# Controller.net
KiCad netlist of a schematic drawn in Altium Designer
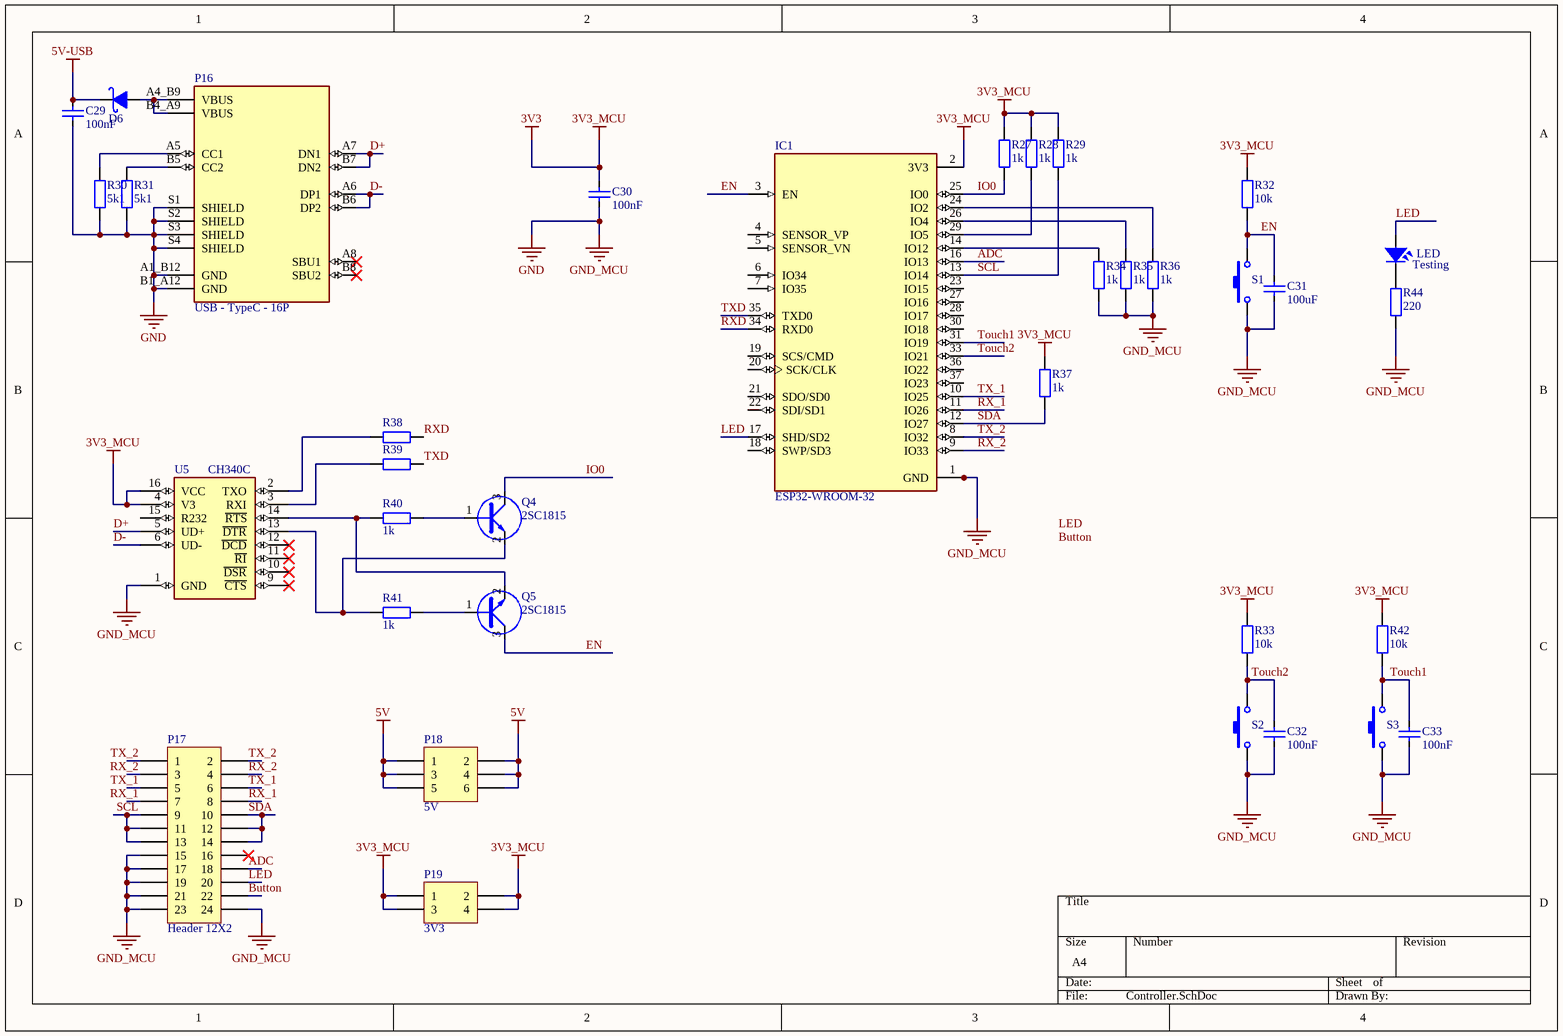
[diagram p0: Controller.SchDoc]

(export (version "E")
  (design (tool "Eeschema 10.0.6"))
  (components
    (comp (ref "C29")
      (value "100nF")
      (footprint "CAP_0805")
      (description "C 0805")
      (fields (field (name "PUBLISHER") "Altium Limited"))
      (libsource (lib "My Library") (part "CapSMD"))
    )
    (comp (ref "C30")
      (value "100nF")
      (footprint "CAP_0805")
      (description "C 0805")
      (fields (field (name "PUBLISHER") "Altium Limited"))
      (libsource (lib "My Library") (part "CapSMD"))
    )
    (comp (ref "C31")
      (value "100uF")
      (footprint "CAP_0805")
      (description "C 0805")
      (fields (field (name "PUBLISHER") "Altium Limited"))
      (libsource (lib "My Library") (part "CapSMD"))
    )
    (comp (ref "C32")
      (value "100nF")
      (footprint "CAP_0805")
      (description "C 0805")
      (fields (field (name "PUBLISHER") "Altium Limited"))
      (libsource (lib "My Library") (part "CapSMD"))
    )
    (comp (ref "C33")
      (value "100nF")
      (footprint "CAP_0805")
      (description "C 0805")
      (fields (field (name "PUBLISHER") "Altium Limited"))
      (libsource (lib "My Library") (part "CapSMD"))
    )
    (comp (ref "D6")
      (value "Diode Schottky")
      (footprint "My Library:DIO-214AA(SMB)")
      (description "SS54")
      (libsource (lib "My Library") (part "Diode Schottky"))
    )
    (comp (ref "IC1")
      (value "ESP32-WROOM-32")
      (footprint "MODULE_ESP32-WROOM-32")
      (description "Bluetooth, WiFi Transceiver Module 2.4GHz ~ 2.5GHz Surface Mount")
      (fields (field (name "MF") "Espressif Systems") (field (name "DIGI-KEY_PART_NUMBER") "1904-1010-1-ND"))
      (libsource (lib "My Library") (part "ESP32-WROOM-32"))
    )
    (comp (ref "LED")
      (value "Testing")
      (footprint "LED-0805-Blue")
      (description "LED Single colour Green and Red")
      (libsource (lib "My Library") (part "LED"))
    )
    (comp (ref "P16")
      (value "USB - TypeC - 16P")
      (footprint "My Library:USB C 16P")
      (libsource (lib "My Library") (part "USB - TypeC - 16P"))
    )
    (comp (ref "P17")
      (value "Header 12X2")
      (footprint "HDR2X12")
      (description "Header, 12-Pin, Dual row")
      (fields (field (name "PUBLISHER") "Altium Limited"))
      (libsource (lib "My Library") (part "Header 12X2"))
    )
    (comp (ref "P18")
      (value "5V")
      (footprint "HDR2X3")
      (description "Header, 3-Pin, Dual row")
      (fields (field (name "PUBLISHER") "Altium Limited"))
      (libsource (lib "My Library") (part "Header 3X2"))
    )
    (comp (ref "P19")
      (value "3V3")
      (footprint "HDR2X2")
      (description "Header, 2-Pin, Dual row")
      (fields (field (name "PUBLISHER") "Altium Limited"))
      (libsource (lib "My Library") (part "Header 2X2"))
    )
    (comp (ref "Q4")
      (value "2SC1815")
      (footprint "SOT23D")
      (description "NPN 600mW, ECB")
      (libsource (lib "My Library") (part "C1815"))
    )
    (comp (ref "Q5")
      (value "2SC1815")
      (footprint "SOT23D")
      (description "NPN 600mW, ECB")
      (libsource (lib "") (part "C1815_1"))
    )
    (comp (ref "R27")
      (value "1k")
      (footprint "RES-SMD-0805")
      (description "R 0805")
      (fields
        (field (name "MANUFACTURER") "Generic Components")
        (field (name "PUBLISHER") "Altium Hobart Technology Centre")
      )
      (libsource (lib "My Library") (part "Resistor - SMD"))
    )
    (comp (ref "R28")
      (value "1k")
      (footprint "RES-SMD-0805")
      (description "R 0805")
      (fields
        (field (name "MANUFACTURER") "Generic Components")
        (field (name "PUBLISHER") "Altium Hobart Technology Centre")
      )
      (libsource (lib "My Library") (part "Resistor - SMD"))
    )
    (comp (ref "R29")
      (value "1k")
      (footprint "RES-SMD-0805")
      (description "R 0805")
      (fields
        (field (name "MANUFACTURER") "Generic Components")
        (field (name "PUBLISHER") "Altium Hobart Technology Centre")
      )
      (libsource (lib "My Library") (part "Resistor - SMD"))
    )
    (comp (ref "R30")
      (value "5k1")
      (footprint "RES-SMD-0805")
      (description "R 0805")
      (fields
        (field (name "MANUFACTURER") "Generic Components")
        (field (name "PUBLISHER") "Altium Hobart Technology Centre")
      )
      (libsource (lib "My Library") (part "Resistor - SMD"))
    )
    (comp (ref "R31")
      (value "5k1")
      (footprint "RES-SMD-0805")
      (description "R 0805")
      (fields
        (field (name "MANUFACTURER") "Generic Components")
        (field (name "PUBLISHER") "Altium Hobart Technology Centre")
      )
      (libsource (lib "My Library") (part "Resistor - SMD"))
    )
    (comp (ref "R32")
      (value "10k")
      (footprint "RES-SMD-0805")
      (description "R 0805")
      (fields
        (field (name "MANUFACTURER") "Generic Components")
        (field (name "PUBLISHER") "Altium Hobart Technology Centre")
      )
      (libsource (lib "My Library") (part "Resistor - SMD"))
    )
    (comp (ref "R33")
      (value "10k")
      (footprint "RES-SMD-0805")
      (description "R 0805")
      (fields
        (field (name "MANUFACTURER") "Generic Components")
        (field (name "PUBLISHER") "Altium Hobart Technology Centre")
      )
      (libsource (lib "My Library") (part "Resistor - SMD"))
    )
    (comp (ref "R34")
      (value "1k")
      (footprint "RES-SMD-0805")
      (description "R 0805")
      (fields
        (field (name "MANUFACTURER") "Generic Components")
        (field (name "PUBLISHER") "Altium Hobart Technology Centre")
      )
      (libsource (lib "My Library") (part "Resistor - SMD"))
    )
    (comp (ref "R35")
      (value "1k")
      (footprint "RES-SMD-0805")
      (description "R 0805")
      (fields
        (field (name "MANUFACTURER") "Generic Components")
        (field (name "PUBLISHER") "Altium Hobart Technology Centre")
      )
      (libsource (lib "My Library") (part "Resistor - SMD"))
    )
    (comp (ref "R36")
      (value "1k")
      (footprint "RES-SMD-0805")
      (description "R 0805")
      (fields
        (field (name "MANUFACTURER") "Generic Components")
        (field (name "PUBLISHER") "Altium Hobart Technology Centre")
      )
      (libsource (lib "My Library") (part "Resistor - SMD"))
    )
    (comp (ref "R37")
      (value "1k")
      (footprint "RES-SMD-0805")
      (description "R 0805")
      (fields
        (field (name "MANUFACTURER") "Generic Components")
        (field (name "PUBLISHER") "Altium Hobart Technology Centre")
      )
      (libsource (lib "My Library") (part "Resistor - SMD"))
    )
    (comp (ref "R38")
      (value "0R")
      (footprint "RES-SMD-0805")
      (description "R 0805")
      (fields
        (field (name "MANUFACTURER") "Generic Components")
        (field (name "PUBLISHER") "Altium Hobart Technology Centre")
      )
      (libsource (lib "My Library") (part "Resistor - SMD"))
    )
    (comp (ref "R39")
      (value "0R")
      (footprint "RES-SMD-0805")
      (description "R 0805")
      (fields
        (field (name "MANUFACTURER") "Generic Components")
        (field (name "PUBLISHER") "Altium Hobart Technology Centre")
      )
      (libsource (lib "My Library") (part "Resistor - SMD"))
    )
    (comp (ref "R40")
      (value "1k")
      (footprint "RES-SMD-0805")
      (description "R 0805")
      (fields
        (field (name "MANUFACTURER") "Generic Components")
        (field (name "PUBLISHER") "Altium Hobart Technology Centre")
      )
      (libsource (lib "My Library") (part "Resistor - SMD"))
    )
    (comp (ref "R41")
      (value "1k")
      (footprint "RES-SMD-0805")
      (description "R 0805")
      (fields
        (field (name "MANUFACTURER") "Generic Components")
        (field (name "PUBLISHER") "Altium Hobart Technology Centre")
      )
      (libsource (lib "My Library") (part "Resistor - SMD"))
    )
    (comp (ref "R42")
      (value "10k")
      (footprint "RES-SMD-0805")
      (description "R 0805")
      (fields
        (field (name "MANUFACTURER") "Generic Components")
        (field (name "PUBLISHER") "Altium Hobart Technology Centre")
      )
      (libsource (lib "My Library") (part "Resistor - SMD"))
    )
    (comp (ref "R44")
      (value "220")
      (footprint "RES-SMD-0805")
      (description "R 0805")
      (fields
        (field (name "MANUFACTURER") "Generic Components")
        (field (name "PUBLISHER") "Altium Hobart Technology Centre")
      )
      (libsource (lib "My Library") (part "Resistor - SMD"))
    )
    (comp (ref "S1")
      (value "SW-SMD")
      (footprint "SW 3x2x4")
      (description "Switch")
      (fields (field (name "PUBLISHER") "Altium Limited"))
      (libsource (lib "My Library") (part "SW-SMD"))
    )
    (comp (ref "S2")
      (value "SW-SMD")
      (footprint "SW 3x2x4")
      (description "Switch")
      (fields (field (name "PUBLISHER") "Altium Limited"))
      (libsource (lib "My Library") (part "SW-SMD"))
    )
    (comp (ref "S3")
      (value "SW-SMD")
      (footprint "SW 3x2x4")
      (description "Switch")
      (fields (field (name "PUBLISHER") "Altium Limited"))
      (libsource (lib "My Library") (part "SW-SMD"))
    )
    (comp (ref "U5")
      (value "CH340C")
      (footprint "SOP-16")
      (description "USB to serial chip CH340")
      (fields (field (name "MF") "WCH"))
      (libsource (lib "My Library") (part "CH340C"))
    )
  )
  (nets
    (net (code "1") (name "/ADC") (class "Default")
      (node (ref "IC1") (pin "16") (pinfunction "IO13_16") (pintype "bidirectional"))
      (node (ref "P17") (pin "18") (pinfunction "18_18") (pintype "passive"))
    )
    (net (code "2") (name "/Button") (class "Default")
      (node (ref "P17") (pin "22") (pinfunction "22_22") (pintype "passive"))
    )
    (net (code "3") (name "/D+") (class "Default")
      (node (ref "P16") (pin "A7") (pinfunction "DN1_A7") (pintype "bidirectional"))
      (node (ref "P16") (pin "B7") (pinfunction "DN2_B7") (pintype "bidirectional"))
      (node (ref "U5") (pin "5") (pinfunction "UD+_5") (pintype "bidirectional"))
    )
    (net (code "4") (name "/D-") (class "Default")
      (node (ref "P16") (pin "A6") (pinfunction "DP1_A6") (pintype "bidirectional"))
      (node (ref "P16") (pin "B6") (pinfunction "DP2_B6") (pintype "bidirectional"))
      (node (ref "U5") (pin "6") (pinfunction "UD-_6") (pintype "bidirectional"))
    )
    (net (code "5") (name "/EN") (class "Default")
      (node (ref "C31") (pin "2") (pinfunction "2_2") (pintype "passive"))
      (node (ref "IC1") (pin "3") (pinfunction "EN_3") (pintype "input"))
      (node (ref "Q5") (pin "3") (pinfunction "C_3") (pintype "passive"))
      (node (ref "R32") (pin "2") (pinfunction "2_2") (pintype "passive"))
      (node (ref "S1") (pin "2") (pinfunction "2_2") (pintype "passive"))
    )
    (net (code "6") (name "/IO0") (class "Default")
      (node (ref "IC1") (pin "25") (pinfunction "IO0_25") (pintype "bidirectional"))
      (node (ref "Q4") (pin "3") (pinfunction "C_3") (pintype "passive"))
      (node (ref "R27") (pin "2") (pinfunction "2_2") (pintype "passive"))
    )
    (net (code "7") (name "/LED") (class "Default")
      (node (ref "IC1") (pin "17") (pinfunction "SHD/SD2_17") (pintype "bidirectional"))
      (node (ref "LED") (pin "1") (pinfunction "1_1") (pintype "passive"))
      (node (ref "P17") (pin "20") (pinfunction "20_20") (pintype "passive"))
    )
    (net (code "8") (name "/RXD") (class "Default")
      (node (ref "IC1") (pin "34") (pinfunction "RXD0_34") (pintype "bidirectional"))
      (node (ref "R38") (pin "1") (pinfunction "1_1") (pintype "passive"))
    )
    (net (code "9") (name "/RX_1") (class "Default")
      (node (ref "IC1") (pin "11") (pinfunction "IO26_11") (pintype "bidirectional"))
      (node (ref "P17") (pin "7") (pinfunction "7_7") (pintype "passive"))
      (node (ref "P17") (pin "8") (pinfunction "8_8") (pintype "passive"))
    )
    (net (code "10") (name "/RX_2") (class "Default")
      (node (ref "IC1") (pin "9") (pinfunction "IO33_9") (pintype "bidirectional"))
      (node (ref "P17") (pin "3") (pinfunction "3_3") (pintype "passive"))
      (node (ref "P17") (pin "4") (pinfunction "4_4") (pintype "passive"))
    )
    (net (code "11") (name "/SCL") (class "Default")
      (node (ref "IC1") (pin "13") (pinfunction "IO14_13") (pintype "bidirectional"))
      (node (ref "P17") (pin "11") (pinfunction "11_11") (pintype "passive"))
      (node (ref "P17") (pin "13") (pinfunction "13_13") (pintype "passive"))
      (node (ref "P17") (pin "9") (pinfunction "9_9") (pintype "passive"))
      (node (ref "R29") (pin "2") (pinfunction "2_2") (pintype "passive"))
    )
    (net (code "12") (name "/SDA") (class "Default")
      (node (ref "IC1") (pin "12") (pinfunction "IO27_12") (pintype "bidirectional"))
      (node (ref "P17") (pin "10") (pinfunction "10_10") (pintype "passive"))
      (node (ref "P17") (pin "12") (pinfunction "12_12") (pintype "passive"))
      (node (ref "P17") (pin "14") (pinfunction "14_14") (pintype "passive"))
      (node (ref "R37") (pin "2") (pinfunction "2_2") (pintype "passive"))
    )
    (net (code "13") (name "/TXD") (class "Default")
      (node (ref "IC1") (pin "35") (pinfunction "TXD0_35") (pintype "bidirectional"))
      (node (ref "R39") (pin "1") (pinfunction "1_1") (pintype "passive"))
    )
    (net (code "14") (name "/TX_1") (class "Default")
      (node (ref "IC1") (pin "10") (pinfunction "IO25_10") (pintype "bidirectional"))
      (node (ref "P17") (pin "5") (pinfunction "5_5") (pintype "passive"))
      (node (ref "P17") (pin "6") (pinfunction "6_6") (pintype "passive"))
    )
    (net (code "15") (name "/TX_2") (class "Default")
      (node (ref "IC1") (pin "8") (pinfunction "IO32_8") (pintype "bidirectional"))
      (node (ref "P17") (pin "1") (pinfunction "1_1") (pintype "passive"))
      (node (ref "P17") (pin "2") (pinfunction "2_2") (pintype "passive"))
    )
    (net (code "16") (name "/Touch1") (class "Default")
      (node (ref "C33") (pin "2") (pinfunction "2_2") (pintype "passive"))
      (node (ref "IC1") (pin "31") (pinfunction "IO19_31") (pintype "bidirectional"))
      (node (ref "R42") (pin "2") (pinfunction "2_2") (pintype "passive"))
      (node (ref "S3") (pin "2") (pinfunction "2_2") (pintype "passive"))
    )
    (net (code "17") (name "/Touch2") (class "Default")
      (node (ref "C32") (pin "2") (pinfunction "2_2") (pintype "passive"))
      (node (ref "IC1") (pin "33") (pinfunction "IO21_33") (pintype "bidirectional"))
      (node (ref "R33") (pin "2") (pinfunction "2_2") (pintype "passive"))
      (node (ref "S2") (pin "2") (pinfunction "2_2") (pintype "passive"))
    )
    (net (code "18") (name "3V3") (class "Default")
      (node (ref "C30") (pin "2") (pinfunction "2_2") (pintype "passive"))
      (node (ref "IC1") (pin "2") (pinfunction "3V3_2") (pintype "power_in"))
      (node (ref "P19") (pin "1") (pinfunction "1_1") (pintype "passive"))
      (node (ref "P19") (pin "2") (pinfunction "2_2") (pintype "passive"))
      (node (ref "P19") (pin "3") (pinfunction "3_3") (pintype "passive"))
      (node (ref "P19") (pin "4") (pinfunction "4_4") (pintype "passive"))
      (node (ref "R27") (pin "1") (pinfunction "1_1") (pintype "passive"))
      (node (ref "R28") (pin "1") (pinfunction "1_1") (pintype "passive"))
      (node (ref "R29") (pin "1") (pinfunction "1_1") (pintype "passive"))
      (node (ref "R32") (pin "1") (pinfunction "1_1") (pintype "passive"))
      (node (ref "R33") (pin "1") (pinfunction "1_1") (pintype "passive"))
      (node (ref "R37") (pin "1") (pinfunction "1_1") (pintype "passive"))
      (node (ref "R42") (pin "1") (pinfunction "1_1") (pintype "passive"))
      (node (ref "U5") (pin "16") (pinfunction "VCC_16") (pintype "bidirectional"))
      (node (ref "U5") (pin "4") (pinfunction "V3_4") (pintype "bidirectional"))
    )
    (net (code "19") (name "5V") (class "Default")
      (node (ref "P18") (pin "1") (pinfunction "1_1") (pintype "passive"))
      (node (ref "P18") (pin "2") (pinfunction "2_2") (pintype "passive"))
      (node (ref "P18") (pin "3") (pinfunction "3_3") (pintype "passive"))
      (node (ref "P18") (pin "4") (pinfunction "4_4") (pintype "passive"))
      (node (ref "P18") (pin "5") (pinfunction "5_5") (pintype "passive"))
      (node (ref "P18") (pin "6") (pinfunction "6_6") (pintype "passive"))
    )
    (net (code "20") (name "5V-USB") (class "Default")
      (node (ref "C29") (pin "2") (pinfunction "2_2") (pintype "passive"))
      (node (ref "D6") (pin "2") (pinfunction "K_2") (pintype "passive"))
    )
    (net (code "21") (name "GND") (class "Default")
      (node (ref "C29") (pin "1") (pinfunction "1_1") (pintype "passive"))
      (node (ref "C30") (pin "1") (pinfunction "1_1") (pintype "passive"))
      (node (ref "C31") (pin "1") (pinfunction "1_1") (pintype "passive"))
      (node (ref "C32") (pin "1") (pinfunction "1_1") (pintype "passive"))
      (node (ref "C33") (pin "1") (pinfunction "1_1") (pintype "passive"))
      (node (ref "IC1") (pin "1") (pinfunction "GND_1") (pintype "power_in"))
      (node (ref "IC1") (pin "15") (pinfunction "GND_15") (pintype "power_in"))
      (node (ref "IC1") (pin "38") (pinfunction "GND_38") (pintype "power_in"))
      (node (ref "IC1") (pin "39_1") (pinfunction "GND_39_1") (pintype "power_in"))
      (node (ref "IC1") (pin "39_10") (pinfunction "GND_39_10") (pintype "power_in"))
      (node (ref "IC1") (pin "39_11") (pinfunction "GND_39_11") (pintype "power_in"))
      (node (ref "IC1") (pin "39_12") (pinfunction "GND_39_12") (pintype "power_in"))
      (node (ref "IC1") (pin "39_13") (pinfunction "GND_39_13") (pintype "power_in"))
      (node (ref "IC1") (pin "39_14") (pinfunction "GND_39_14") (pintype "power_in"))
      (node (ref "IC1") (pin "39_15") (pinfunction "GND_39_15") (pintype "power_in"))
      (node (ref "IC1") (pin "39_16") (pinfunction "GND_39_16") (pintype "power_in"))
      (node (ref "IC1") (pin "39_17") (pinfunction "GND_39_17") (pintype "power_in"))
      (node (ref "IC1") (pin "39_18") (pinfunction "GND_39_18") (pintype "power_in"))
      (node (ref "IC1") (pin "39_19") (pinfunction "GND_39_19") (pintype "power_in"))
      (node (ref "IC1") (pin "39_2") (pinfunction "GND_39_2") (pintype "power_in"))
      (node (ref "IC1") (pin "39_20") (pinfunction "GND_39_20") (pintype "power_in"))
      (node (ref "IC1") (pin "39_21") (pinfunction "GND_39_21") (pintype "power_in"))
      (node (ref "IC1") (pin "39_3") (pinfunction "GND_39_3") (pintype "power_in"))
      (node (ref "IC1") (pin "39_4") (pinfunction "GND_39_4") (pintype "power_in"))
      (node (ref "IC1") (pin "39_5") (pinfunction "GND_39_5") (pintype "power_in"))
      (node (ref "IC1") (pin "39_6") (pinfunction "GND_39_6") (pintype "power_in"))
      (node (ref "IC1") (pin "39_7") (pinfunction "GND_39_7") (pintype "power_in"))
      (node (ref "IC1") (pin "39_8") (pinfunction "GND_39_8") (pintype "power_in"))
      (node (ref "IC1") (pin "39_9") (pinfunction "GND_39_9") (pintype "power_in"))
      (node (ref "P16") (pin "A1_B12") (pinfunction "GND_A1_B12") (pintype "power_in"))
      (node (ref "P16") (pin "B1_A12") (pinfunction "GND_B1_A12") (pintype "power_in"))
      (node (ref "P16") (pin "S1") (pinfunction "SHIELD_S1") (pintype "passive"))
      (node (ref "P16") (pin "S2") (pinfunction "SHIELD_S2") (pintype "passive"))
      (node (ref "P16") (pin "S3") (pinfunction "SHIELD_S3") (pintype "passive"))
      (node (ref "P16") (pin "S4") (pinfunction "SHIELD_S4") (pintype "passive"))
      (node (ref "P17") (pin "15") (pinfunction "15_15") (pintype "passive"))
      (node (ref "P17") (pin "17") (pinfunction "17_17") (pintype "passive"))
      (node (ref "P17") (pin "19") (pinfunction "19_19") (pintype "passive"))
      (node (ref "P17") (pin "21") (pinfunction "21_21") (pintype "passive"))
      (node (ref "P17") (pin "23") (pinfunction "23_23") (pintype "passive"))
      (node (ref "P17") (pin "24") (pinfunction "24_24") (pintype "passive"))
      (node (ref "R30") (pin "2") (pinfunction "2_2") (pintype "passive"))
      (node (ref "R31") (pin "2") (pinfunction "2_2") (pintype "passive"))
      (node (ref "R34") (pin "2") (pinfunction "2_2") (pintype "passive"))
      (node (ref "R35") (pin "2") (pinfunction "2_2") (pintype "passive"))
      (node (ref "R36") (pin "1") (pinfunction "1_1") (pintype "passive"))
      (node (ref "R44") (pin "2") (pinfunction "2_2") (pintype "passive"))
      (node (ref "S1") (pin "1") (pinfunction "1_1") (pintype "passive"))
      (node (ref "S2") (pin "1") (pinfunction "1_1") (pintype "passive"))
      (node (ref "S3") (pin "1") (pinfunction "1_1") (pintype "passive"))
      (node (ref "U5") (pin "1") (pinfunction "GND_1") (pintype "bidirectional"))
    )
    (net (code "22") (name "Net-(D6-A)") (class "Default")
      (node (ref "D6") (pin "1") (pinfunction "A_1") (pintype "passive"))
      (node (ref "P16") (pin "A4_B9") (pinfunction "VBUS_A4_B9") (pintype "power_in"))
      (node (ref "P16") (pin "B4_A9") (pinfunction "VBUS_B4_A9") (pintype "power_in"))
    )
    (net (code "23") (name "Net-(IC1-IO2)") (class "Default")
      (node (ref "IC1") (pin "24") (pinfunction "IO2_24") (pintype "bidirectional"))
      (node (ref "R36") (pin "2") (pinfunction "2_2") (pintype "passive"))
    )
    (net (code "24") (name "Net-(IC1-IO4)") (class "Default")
      (node (ref "IC1") (pin "26") (pinfunction "IO4_26") (pintype "bidirectional"))
      (node (ref "R35") (pin "1") (pinfunction "1_1") (pintype "passive"))
    )
    (net (code "25") (name "Net-(IC1-IO5)") (class "Default")
      (node (ref "IC1") (pin "29") (pinfunction "IO5_29") (pintype "bidirectional"))
      (node (ref "R28") (pin "2") (pinfunction "2_2") (pintype "passive"))
    )
    (net (code "26") (name "Net-(IC1-IO12)") (class "Default")
      (node (ref "IC1") (pin "14") (pinfunction "IO12_14") (pintype "bidirectional"))
      (node (ref "R34") (pin "1") (pinfunction "1_1") (pintype "passive"))
    )
    (net (code "27") (name "Net-(LED-Pad2)") (class "Default")
      (node (ref "LED") (pin "2") (pinfunction "2_2") (pintype "passive"))
      (node (ref "R44") (pin "1") (pinfunction "1_1") (pintype "passive"))
    )
    (net (code "28") (name "Net-(P16-CC1)") (class "Default")
      (node (ref "P16") (pin "A5") (pinfunction "CC1_A5") (pintype "bidirectional"))
      (node (ref "R30") (pin "1") (pinfunction "1_1") (pintype "passive"))
    )
    (net (code "29") (name "Net-(P16-CC2)") (class "Default")
      (node (ref "P16") (pin "B5") (pinfunction "CC2_B5") (pintype "bidirectional"))
      (node (ref "R31") (pin "1") (pinfunction "1_1") (pintype "passive"))
    )
    (net (code "30") (name "Net-(Q4-B)") (class "Default")
      (node (ref "Q4") (pin "1") (pinfunction "B_1") (pintype "passive"))
      (node (ref "R40") (pin "1") (pinfunction "1_1") (pintype "passive"))
    )
    (net (code "31") (name "Net-(Q4-E)") (class "Default")
      (node (ref "Q4") (pin "2") (pinfunction "E_2") (pintype "passive"))
      (node (ref "R41") (pin "2") (pinfunction "2_2") (pintype "passive"))
      (node (ref "U5") (pin "13") (pinfunction "~{DTR}_13") (pintype "bidirectional"))
    )
    (net (code "32") (name "Net-(Q5-B)") (class "Default")
      (node (ref "Q5") (pin "1") (pinfunction "B_1") (pintype "passive"))
      (node (ref "R41") (pin "1") (pinfunction "1_1") (pintype "passive"))
    )
    (net (code "33") (name "Net-(Q5-E)") (class "Default")
      (node (ref "Q5") (pin "2") (pinfunction "E_2") (pintype "passive"))
      (node (ref "R40") (pin "2") (pinfunction "2_2") (pintype "passive"))
      (node (ref "U5") (pin "14") (pinfunction "~{RTS}_14") (pintype "bidirectional"))
    )
    (net (code "34") (name "Net-(U5-RXI)") (class "Default")
      (node (ref "R39") (pin "2") (pinfunction "2_2") (pintype "passive"))
      (node (ref "U5") (pin "3") (pinfunction "RXI_3") (pintype "bidirectional"))
    )
    (net (code "35") (name "Net-(U5-TXO)") (class "Default")
      (node (ref "R38") (pin "2") (pinfunction "2_2") (pintype "passive"))
      (node (ref "U5") (pin "2") (pinfunction "TXO_2") (pintype "bidirectional"))
    )
    (net (code "36") (name "unconnected-(IC1-IO15-Pad23)") (class "Default")
      (node (ref "IC1") (pin "23") (pinfunction "IO15_23") (pintype "bidirectional"))
    )
    (net (code "37") (name "unconnected-(IC1-IO16-Pad27)") (class "Default")
      (node (ref "IC1") (pin "27") (pinfunction "IO16_27") (pintype "bidirectional"))
    )
    (net (code "38") (name "unconnected-(IC1-IO17-Pad28)") (class "Default")
      (node (ref "IC1") (pin "28") (pinfunction "IO17_28") (pintype "bidirectional"))
    )
    (net (code "39") (name "unconnected-(IC1-IO18-Pad30)") (class "Default")
      (node (ref "IC1") (pin "30") (pinfunction "IO18_30") (pintype "bidirectional"))
    )
    (net (code "40") (name "unconnected-(IC1-IO22-Pad36)") (class "Default")
      (node (ref "IC1") (pin "36") (pinfunction "IO22_36") (pintype "bidirectional"))
    )
    (net (code "41") (name "unconnected-(IC1-IO23-Pad37)") (class "Default")
      (node (ref "IC1") (pin "37") (pinfunction "IO23_37") (pintype "bidirectional"))
    )
    (net (code "42") (name "unconnected-(IC1-IO34-Pad6)") (class "Default")
      (node (ref "IC1") (pin "6") (pinfunction "IO34_6") (pintype "input"))
    )
    (net (code "43") (name "unconnected-(IC1-IO35-Pad7)") (class "Default")
      (node (ref "IC1") (pin "7") (pinfunction "IO35_7") (pintype "input"))
    )
    (net (code "44") (name "unconnected-(IC1-SCK{slash}CLK-Pad20)") (class "Default")
      (node (ref "IC1") (pin "20") (pinfunction "SCK/CLK_20") (pintype "bidirectional"))
    )
    (net (code "45") (name "unconnected-(IC1-SCS{slash}CMD-Pad19)") (class "Default")
      (node (ref "IC1") (pin "19") (pinfunction "SCS/CMD_19") (pintype "bidirectional"))
    )
    (net (code "46") (name "unconnected-(IC1-SDI{slash}SD1-Pad22)") (class "Default")
      (node (ref "IC1") (pin "22") (pinfunction "SDI/SD1_22") (pintype "bidirectional"))
    )
    (net (code "47") (name "unconnected-(IC1-SDO{slash}SD0-Pad21)") (class "Default")
      (node (ref "IC1") (pin "21") (pinfunction "SDO/SD0_21") (pintype "bidirectional"))
    )
    (net (code "48") (name "unconnected-(IC1-SENSOR_VN-Pad5)") (class "Default")
      (node (ref "IC1") (pin "5") (pinfunction "SENSOR_VN_5") (pintype "input"))
    )
    (net (code "49") (name "unconnected-(IC1-SENSOR_VP-Pad4)") (class "Default")
      (node (ref "IC1") (pin "4") (pinfunction "SENSOR_VP_4") (pintype "input"))
    )
    (net (code "50") (name "unconnected-(IC1-SWP{slash}SD3-Pad18)") (class "Default")
      (node (ref "IC1") (pin "18") (pinfunction "SWP/SD3_18") (pintype "bidirectional"))
    )
    (net (code "51") (name "unconnected-(P16-SBU1-PadA8)") (class "Default")
      (node (ref "P16") (pin "A8") (pinfunction "SBU1_A8") (pintype "bidirectional+no_connect"))
    )
    (net (code "52") (name "unconnected-(P16-SBU2-PadB8)") (class "Default")
      (node (ref "P16") (pin "B8") (pinfunction "SBU2_B8") (pintype "bidirectional+no_connect"))
    )
    (net (code "53") (name "unconnected-(P17-Pad16)") (class "Default")
      (node (ref "P17") (pin "16") (pinfunction "16_16") (pintype "passive+no_connect"))
    )
    (net (code "54") (name "unconnected-(U5-R232-Pad15)") (class "Default")
      (node (ref "U5") (pin "15") (pinfunction "R232_15") (pintype "bidirectional"))
    )
    (net (code "55") (name "unconnected-(U5-~{CTS}-Pad9)") (class "Default")
      (node (ref "U5") (pin "9") (pinfunction "~{CTS}_9") (pintype "bidirectional+no_connect"))
    )
    (net (code "56") (name "unconnected-(U5-~{DCD}-Pad12)") (class "Default")
      (node (ref "U5") (pin "12") (pinfunction "~{DCD}_12") (pintype "bidirectional+no_connect"))
    )
    (net (code "57") (name "unconnected-(U5-~{DSR}-Pad10)") (class "Default")
      (node (ref "U5") (pin "10") (pinfunction "~{DSR}_10") (pintype "bidirectional+no_connect"))
    )
    (net (code "58") (name "unconnected-(U5-~{RI}-Pad11)") (class "Default")
      (node (ref "U5") (pin "11") (pinfunction "~{RI}_11") (pintype "bidirectional+no_connect"))
    )
  )
)
